# 3_Communication.net
KiCad netlist of a schematic drawn in Altium Designer
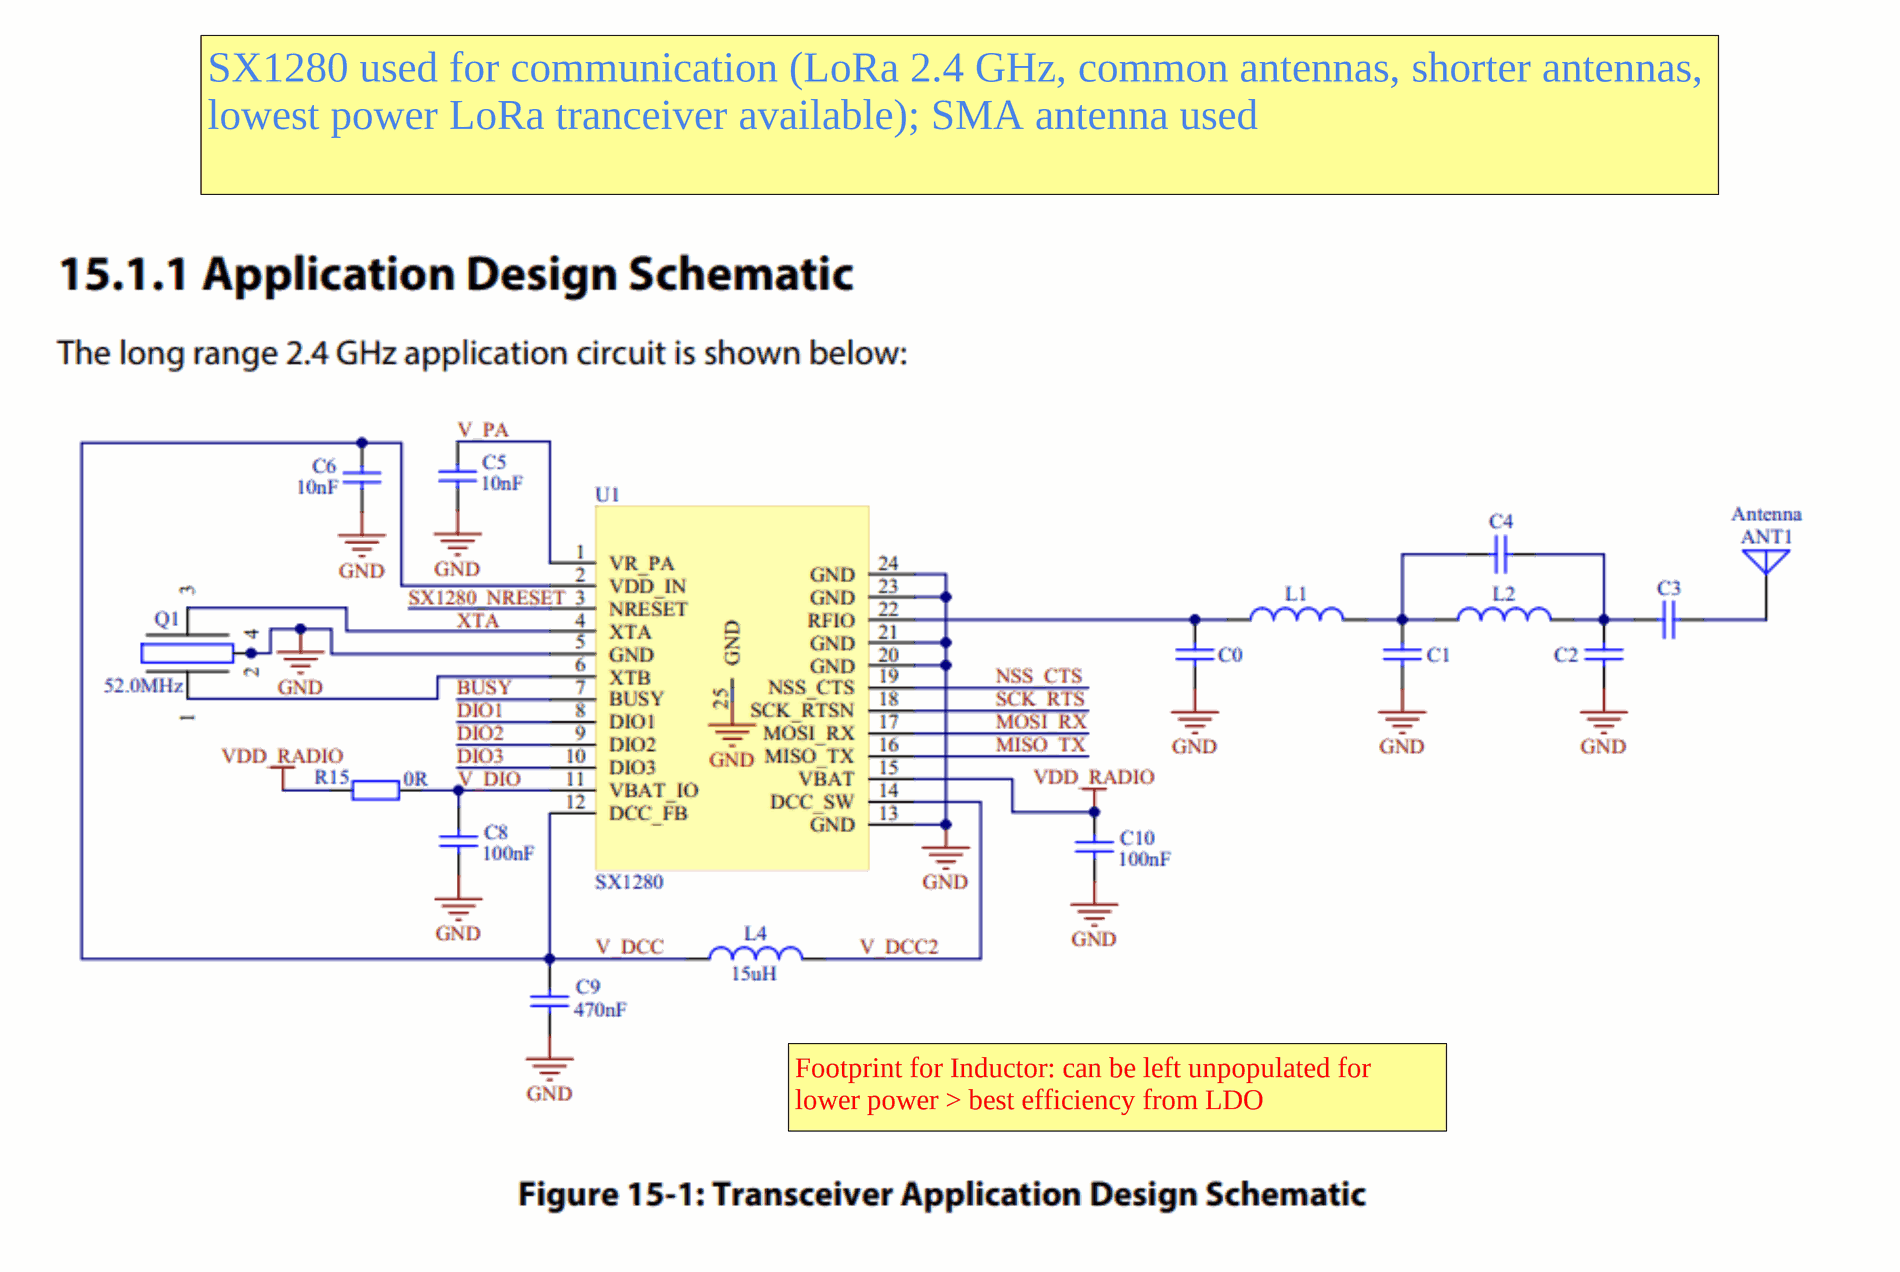
[diagram p0: 3_Communication.SchDoc, left]
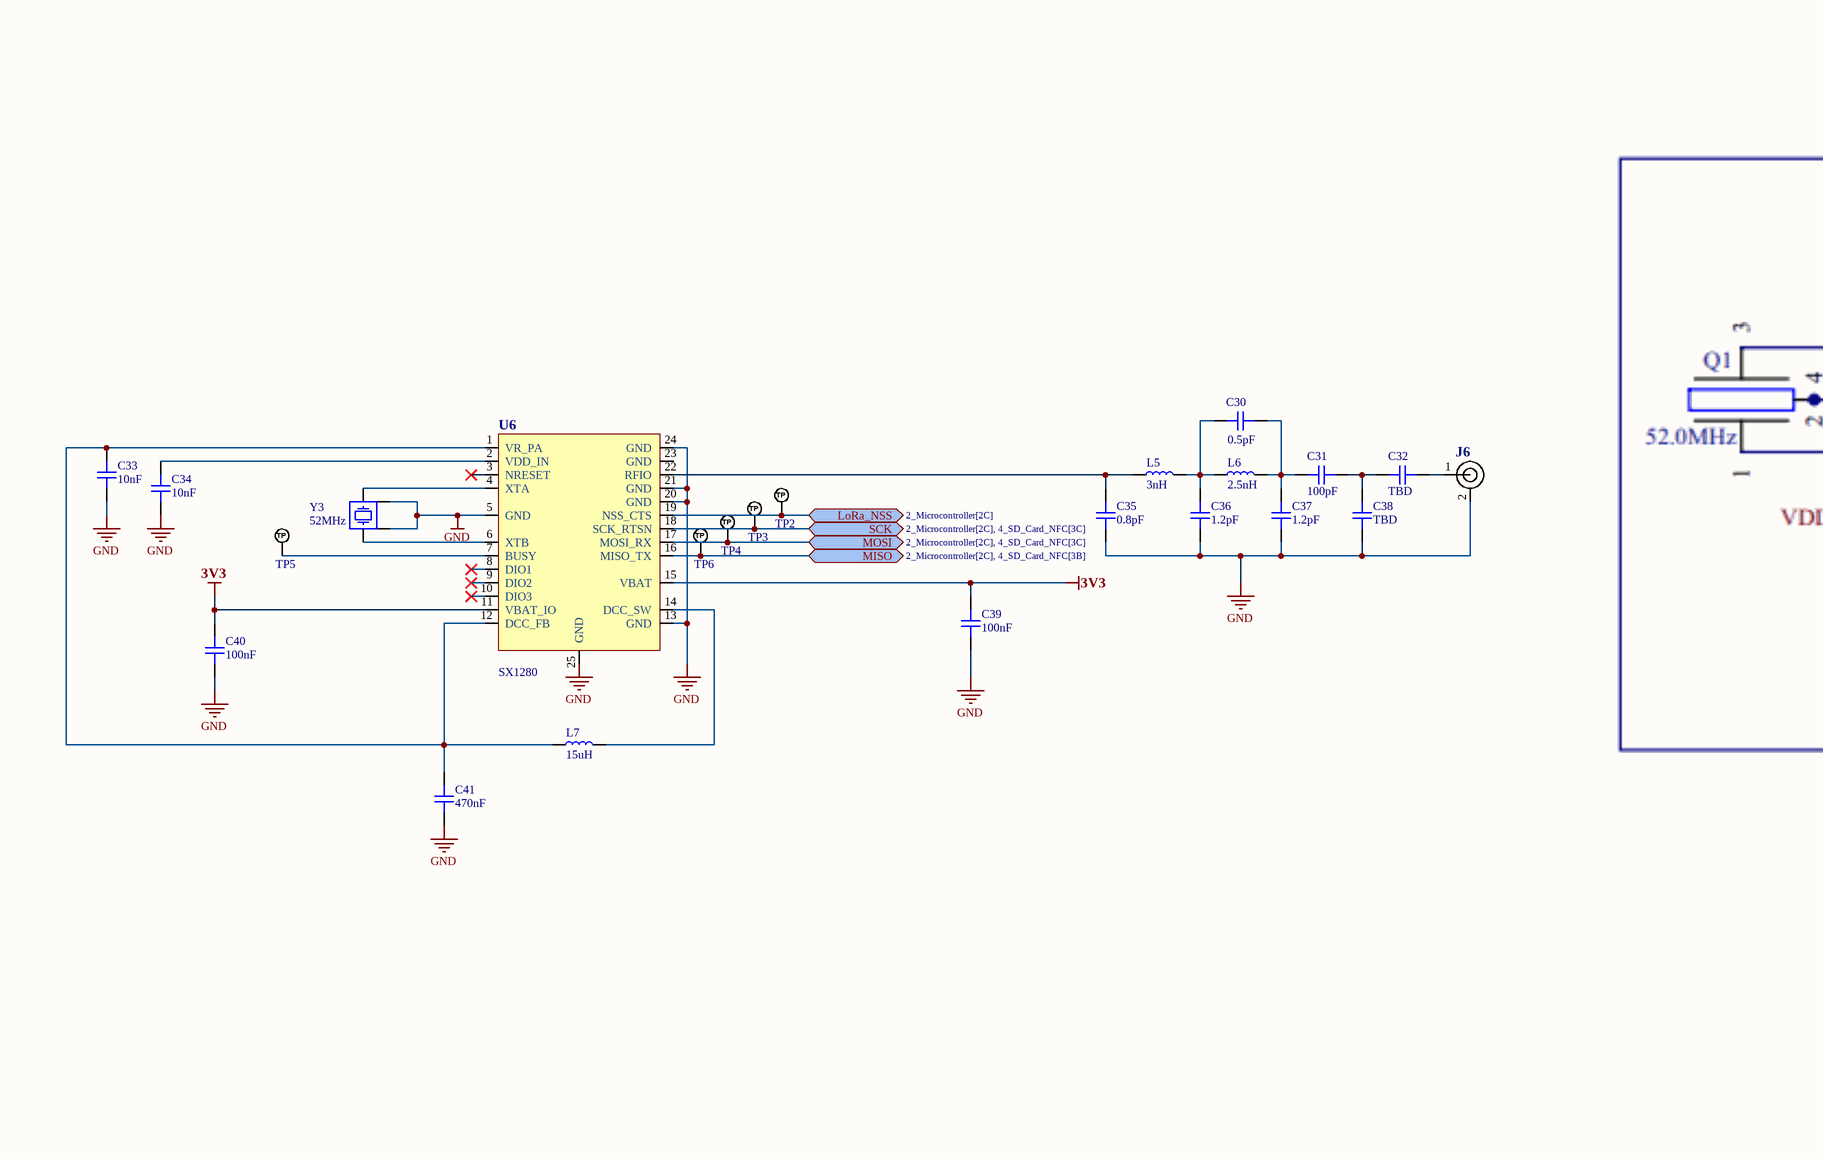
[diagram p1: 3_Communication.SchDoc, middle]
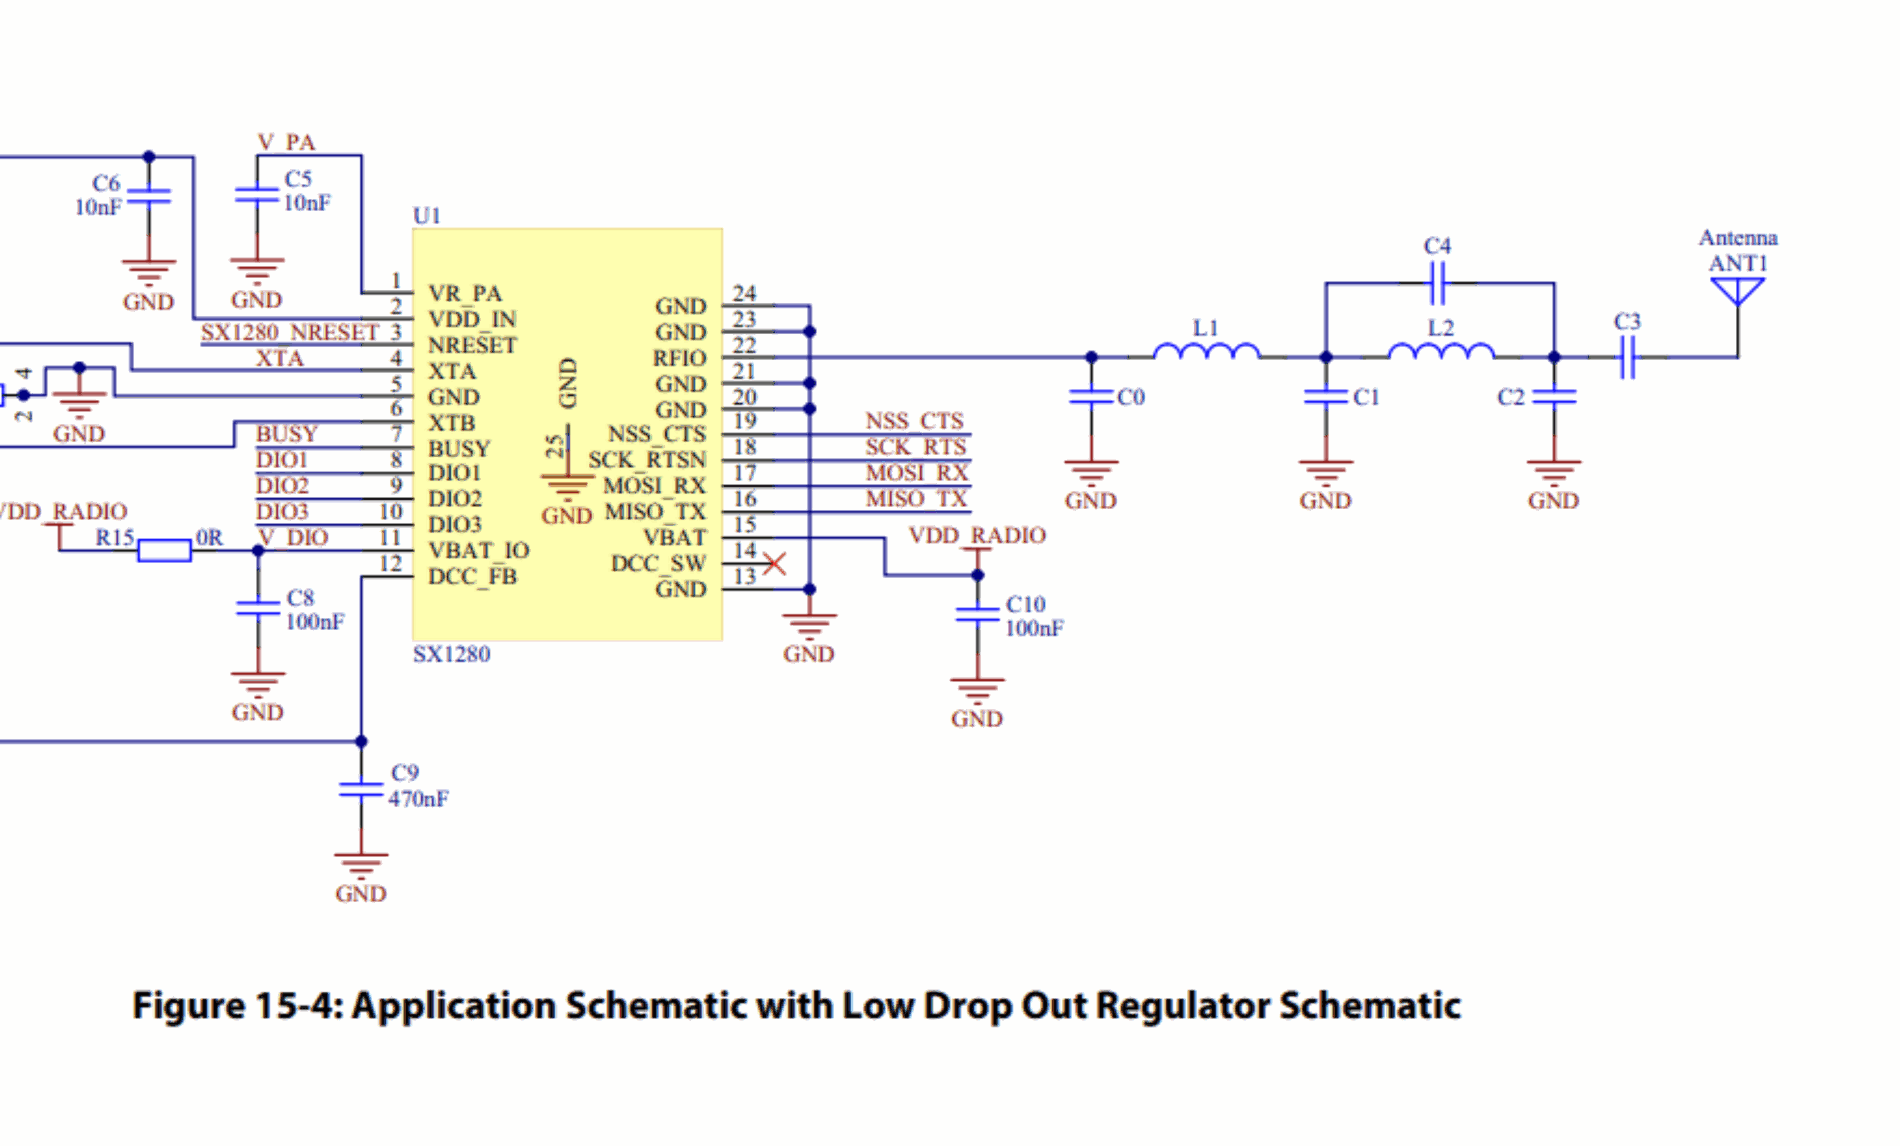
[diagram p2: 3_Communication.SchDoc, right]

(export (version "E")
  (design (tool "Eeschema 10.0.6"))
  (components
    (comp (ref "C30")
      (value "0.5pF")
      (footprint "C0603")
      (description "Capacitor SMD 0603")
      (libsource (lib "Schlib_H2") (part "CAP_0603"))
    )
    (comp (ref "C31")
      (value "100pF")
      (footprint "C0603")
      (description "Capacitor SMD 0603")
      (libsource (lib "Schlib_H2") (part "CAP_0603"))
    )
    (comp (ref "C32")
      (value "TBD")
      (footprint "C0603")
      (description "Capacitor SMD 0805")
      (libsource (lib "Schlib_H2") (part "CAP_0603"))
    )
    (comp (ref "C33")
      (value "10nF")
      (footprint "C0603")
      (description "Capacitor SMD 0603")
      (libsource (lib "Schlib_H2") (part "CAP_0603"))
    )
    (comp (ref "C34")
      (value "10nF")
      (footprint "C0603")
      (description "Capacitor SMD 0603")
      (libsource (lib "Schlib_H2") (part "CAP_0603"))
    )
    (comp (ref "C35")
      (value "0.8pF")
      (footprint "C0603")
      (description "Capacitor SMD 0805")
      (libsource (lib "Schlib_H2") (part "CAP_0805"))
    )
    (comp (ref "C36")
      (value "1.2pF")
      (footprint "C0603")
      (description "Capacitor SMD 0603")
      (libsource (lib "Schlib_H2") (part "CAP_0603"))
    )
    (comp (ref "C37")
      (value "1.2pF")
      (footprint "C0603")
      (description "Capacitor SMD 0603")
      (libsource (lib "Schlib_H2") (part "CAP_0603"))
    )
    (comp (ref "C38")
      (value "TBD")
      (footprint "C0603")
      (description "Capacitor SMD 0805")
      (libsource (lib "Schlib_H2") (part "CAP_0603"))
    )
    (comp (ref "C39")
      (value "100nF")
      (footprint "C0603")
      (description "Capacitor SMD 0603")
      (libsource (lib "Schlib_H2") (part "CAP_0603"))
    )
    (comp (ref "C40")
      (value "100nF")
      (footprint "C0603")
      (description "Capacitor SMD 0603")
      (libsource (lib "Schlib_H2") (part "CAP_0603"))
    )
    (comp (ref "C41")
      (value "470nF")
      (footprint "C0603")
      (description "Capacitor SMD 0603")
      (libsource (lib "Schlib_H2") (part "CAP_0603"))
    )
    (comp (ref "J6")
      (value "SMA_EDGE_CONN")
      (footprint "CON_SMA-EDGE-S")
      (description "RF Connector SMA Female 50 Ohms 18 GHz PCB Edge Mount")
      (fields
        (field (name "MANUFACTURER") "RF Solutions")
        (field (name "MANUFACTURER PART NUMBER") "CON-SMA-EDGE-S")
      )
      (libsource (lib "Schlib_H2") (part "CON-SMA-EDGE-S"))
    )
    (comp (ref "L5")
      (value "3nH")
      (footprint "L0603")
      (description "Inductor SMD 0603")
      (libsource (lib "Schlib_H2") (part "IND_0603"))
    )
    (comp (ref "L6")
      (value "2.5nH")
      (footprint "L0603")
      (description "Inductor SMD 0603")
      (libsource (lib "Schlib_H2") (part "IND_0603"))
    )
    (comp (ref "L7")
      (value "15uH")
      (footprint "IND_3.2_4")
      (description "Inductor SMD 0603")
      (libsource (lib "Schlib_H2") (part "IND_0603"))
    )
    (comp (ref "TP2")
      (value "TP_NOBOM")
      (footprint "TEST_PAD_THD")
      (description "Test Point Round 1mm (NO BOM)")
      (libsource (lib "Schlib_H2") (part "TEST_POINT_RND_1MM"))
    )
    (comp (ref "TP3")
      (value "TP_NOBOM")
      (footprint "TEST_PAD_THD")
      (description "Test Point Round 1mm (NO BOM)")
      (libsource (lib "Schlib_H2") (part "TEST_POINT_RND_1MM"))
    )
    (comp (ref "TP4")
      (value "TP_NOBOM")
      (footprint "TEST_PAD_THD")
      (description "Test Point Round 1mm (NO BOM)")
      (libsource (lib "Schlib_H2") (part "TEST_POINT_RND_1MM"))
    )
    (comp (ref "TP5")
      (value "TP_NOBOM")
      (footprint "TEST_PAD_THD")
      (description "Test Point Round 1mm (NO BOM)")
      (libsource (lib "Schlib_H2") (part "TEST_POINT_RND_1MM"))
    )
    (comp (ref "TP6")
      (value "TP_NOBOM")
      (footprint "TEST_PAD_THD")
      (description "Test Point Round 1mm (NO BOM)")
      (libsource (lib "Schlib_H2") (part "TEST_POINT_RND_1MM"))
    )
    (comp (ref "U6")
      (value "SX1280")
      (footprint "QFN-24_4x4_0.5")
      (description "Low power LoRa transceiver operating at 2.4GHz with ranging capability")
      (libsource (lib "Schlib_H2") (part "SX1280"))
    )
    (comp (ref "Y3")
      (value "52MHz")
      (footprint "CRYSTAL_2016_4P")
      (description "Crystal")
      (fields
        (field (name "MANUFACTURER") "Epson")
        (field (name "MANUFACTURER PART NUMBER") "TSX-3225 24.0000MF15X-AC")
      )
      (libsource (lib "Schlib_H2") (part "Crystal"))
    )
  )
  (nets
    (net (code "1") (name "/LoRa_NSS") (class "Default")
      (node (ref "TP2") (pin "1") (pinfunction "TP_1") (pintype "passive"))
      (node (ref "U6") (pin "19") (pinfunction "NSS_CTS_19") (pintype "passive"))
    )
    (net (code "2") (name "/MISO") (class "Default")
      (node (ref "TP6") (pin "1") (pinfunction "TP_1") (pintype "passive"))
      (node (ref "U6") (pin "16") (pinfunction "MISO_TX_16") (pintype "passive"))
    )
    (net (code "3") (name "/MOSI") (class "Default")
      (node (ref "TP4") (pin "1") (pinfunction "TP_1") (pintype "passive"))
      (node (ref "U6") (pin "17") (pinfunction "MOSI_RX_17") (pintype "passive"))
    )
    (net (code "4") (name "/SCK") (class "Default")
      (node (ref "TP3") (pin "1") (pinfunction "TP_1") (pintype "passive"))
      (node (ref "U6") (pin "18") (pinfunction "SCK_RTSN_18") (pintype "passive"))
    )
    (net (code "5") (name "3V3") (class "Default")
      (node (ref "C39") (pin "2") (pinfunction "2_2") (pintype "passive"))
      (node (ref "C40") (pin "2") (pinfunction "2_2") (pintype "passive"))
      (node (ref "U6") (pin "11") (pinfunction "VBAT_IO_11") (pintype "passive"))
      (node (ref "U6") (pin "15") (pinfunction "VBAT_15") (pintype "passive"))
    )
    (net (code "6") (name "GND") (class "Default")
      (node (ref "C33") (pin "1") (pinfunction "1_1") (pintype "passive"))
      (node (ref "C34") (pin "1") (pinfunction "1_1") (pintype "passive"))
      (node (ref "C35") (pin "1") (pinfunction "1_1") (pintype "passive"))
      (node (ref "C36") (pin "1") (pinfunction "1_1") (pintype "passive"))
      (node (ref "C37") (pin "1") (pinfunction "1_1") (pintype "passive"))
      (node (ref "C38") (pin "1") (pinfunction "1_1") (pintype "passive"))
      (node (ref "C39") (pin "1") (pinfunction "1_1") (pintype "passive"))
      (node (ref "C40") (pin "1") (pinfunction "1_1") (pintype "passive"))
      (node (ref "C41") (pin "1") (pinfunction "1_1") (pintype "passive"))
      (node (ref "J6") (pin "2") (pinfunction "2_2") (pintype "passive"))
      (node (ref "U6") (pin "13") (pinfunction "GND_13") (pintype "passive"))
      (node (ref "U6") (pin "20") (pinfunction "GND_20") (pintype "passive"))
      (node (ref "U6") (pin "21") (pinfunction "GND_21") (pintype "passive"))
      (node (ref "U6") (pin "24") (pinfunction "GND_24") (pintype "passive"))
      (node (ref "U6") (pin "25") (pinfunction "GND_25") (pintype "passive"))
      (node (ref "U6") (pin "5") (pinfunction "GND_5") (pintype "passive"))
      (node (ref "Y3") (pin "2") (pinfunction "2_2") (pintype "passive"))
      (node (ref "Y3") (pin "4") (pinfunction "4_4") (pintype "passive"))
    )
    (net (code "7") (name "Net-(C30-Pad1)") (class "Default")
      (node (ref "C30") (pin "1") (pinfunction "1_1") (pintype "passive"))
      (node (ref "C31") (pin "2") (pinfunction "2_2") (pintype "passive"))
      (node (ref "C37") (pin "2") (pinfunction "2_2") (pintype "passive"))
      (node (ref "L6") (pin "2") (pinfunction "2_2") (pintype "passive"))
    )
    (net (code "8") (name "Net-(C30-Pad2)") (class "Default")
      (node (ref "C30") (pin "2") (pinfunction "2_2") (pintype "passive"))
      (node (ref "C36") (pin "2") (pinfunction "2_2") (pintype "passive"))
      (node (ref "L5") (pin "2") (pinfunction "2_2") (pintype "passive"))
      (node (ref "L6") (pin "1") (pinfunction "1_1") (pintype "passive"))
    )
    (net (code "9") (name "Net-(C31-Pad1)") (class "Default")
      (node (ref "C31") (pin "1") (pinfunction "1_1") (pintype "passive"))
      (node (ref "C32") (pin "2") (pinfunction "2_2") (pintype "passive"))
      (node (ref "C38") (pin "2") (pinfunction "2_2") (pintype "passive"))
    )
    (net (code "10") (name "Net-(C32-Pad1)") (class "Default")
      (node (ref "C32") (pin "1") (pinfunction "1_1") (pintype "passive"))
      (node (ref "J6") (pin "1") (pinfunction "1_1") (pintype "passive"))
    )
    (net (code "11") (name "Net-(TP5-TP)") (class "Default")
      (node (ref "TP5") (pin "1") (pinfunction "TP_1") (pintype "passive"))
      (node (ref "U6") (pin "7") (pinfunction "BUSY_7") (pintype "passive"))
    )
    (net (code "12") (name "Net-(U6-DCC_FB)") (class "Default")
      (node (ref "C33") (pin "2") (pinfunction "2_2") (pintype "passive"))
      (node (ref "C41") (pin "2") (pinfunction "2_2") (pintype "passive"))
      (node (ref "L7") (pin "1") (pinfunction "1_1") (pintype "passive"))
      (node (ref "U6") (pin "1") (pinfunction "VR_PA_1") (pintype "passive"))
      (node (ref "U6") (pin "12") (pinfunction "DCC_FB_12") (pintype "passive"))
    )
    (net (code "13") (name "Net-(U6-DCC_SW)") (class "Default")
      (node (ref "L7") (pin "2") (pinfunction "2_2") (pintype "passive"))
      (node (ref "U6") (pin "14") (pinfunction "DCC_SW_14") (pintype "passive"))
    )
    (net (code "14") (name "Net-(U6-RFIO)") (class "Default")
      (node (ref "C35") (pin "2") (pinfunction "2_2") (pintype "passive"))
      (node (ref "L5") (pin "1") (pinfunction "1_1") (pintype "passive"))
      (node (ref "U6") (pin "22") (pinfunction "RFIO_22") (pintype "passive"))
    )
    (net (code "15") (name "Net-(U6-VDD_IN)") (class "Default")
      (node (ref "C34") (pin "2") (pinfunction "2_2") (pintype "passive"))
      (node (ref "U6") (pin "2") (pinfunction "VDD_IN_2") (pintype "passive"))
    )
    (net (code "16") (name "Net-(U6-XTA)") (class "Default")
      (node (ref "U6") (pin "4") (pinfunction "XTA_4") (pintype "passive"))
      (node (ref "Y3") (pin "3") (pinfunction "3_3") (pintype "passive"))
    )
    (net (code "17") (name "Net-(U6-XTB)") (class "Default")
      (node (ref "U6") (pin "6") (pinfunction "XTB_6") (pintype "passive"))
      (node (ref "Y3") (pin "1") (pinfunction "1_1") (pintype "passive"))
    )
    (net (code "18") (name "unconnected-(U6-DIO1-Pad8)") (class "Default")
      (node (ref "U6") (pin "8") (pinfunction "DIO1_8") (pintype "passive+no_connect"))
    )
    (net (code "19") (name "unconnected-(U6-DIO2-Pad9)") (class "Default")
      (node (ref "U6") (pin "9") (pinfunction "DIO2_9") (pintype "passive+no_connect"))
    )
    (net (code "20") (name "unconnected-(U6-DIO3-Pad10)") (class "Default")
      (node (ref "U6") (pin "10") (pinfunction "DIO3_10") (pintype "passive+no_connect"))
    )
    (net (code "21") (name "unconnected-(U6-GND-Pad23)") (class "Default")
      (node (ref "U6") (pin "23") (pinfunction "GND_23") (pintype "passive"))
    )
    (net (code "22") (name "unconnected-(U6-NRESET-Pad3)") (class "Default")
      (node (ref "U6") (pin "3") (pinfunction "NRESET_3") (pintype "passive+no_connect"))
    )
  )
)
